# SolderingStation-v2_2026-06-25.net
KiCad netlist of a schematic drawn in Altium Designer
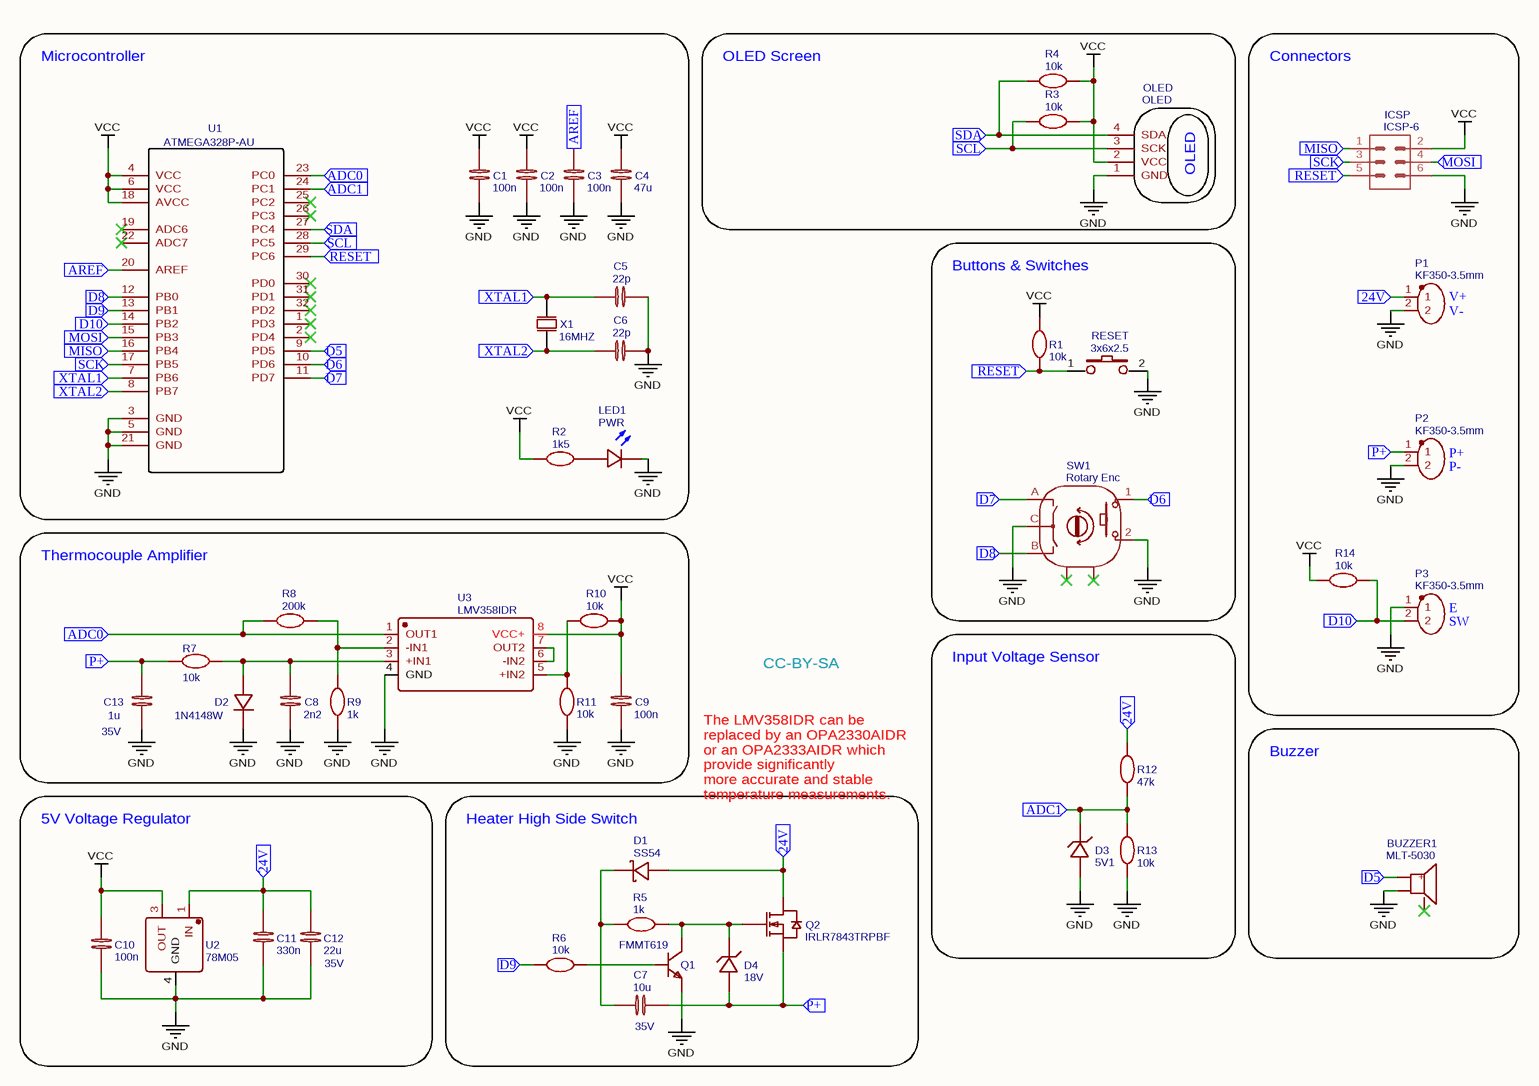
[diagram p0: SolderingStation-v2_2026-06-25.schdoc]

(export (version "E")
  (design (tool "Eeschema 10.0.6"))
  (components
    (comp (ref "BUZZER1")
      (value "MLT-5030")
      (footprint "MLT-5030")
      (fields (field (name "MANUFACTURER") "HNDZ"))
      (libsource (lib "altium-import") (part "root_0_MLT-5030_"))
    )
    (comp (ref "C1")
      (value "100n")
      (footprint "0603")
      (fields (field (name "MANUFACTURER PART") "CC0603KRX7R9BB104") (field (name "MANUFACTURER") "YAGEO"))
      (libsource (lib "altium-import") (part "root_0_100n_"))
    )
    (comp (ref "C2")
      (value "100n")
      (footprint "0603")
      (fields (field (name "MANUFACTURER PART") "CC0603KRX7R9BB104") (field (name "MANUFACTURER") "YAGEO"))
      (libsource (lib "altium-import") (part "root_0_100n_"))
    )
    (comp (ref "C3")
      (value "100n")
      (footprint "0603")
      (fields (field (name "MANUFACTURER PART") "CC0603KRX7R9BB104") (field (name "MANUFACTURER") "YAGEO"))
      (libsource (lib "altium-import") (part "root_0_100n_"))
    )
    (comp (ref "C4")
      (value "47u")
      (footprint "1206")
      (fields (field (name "MANUFACTURER PART") "1206F476M100NT") (field (name "MANUFACTURER") "FH"))
      (libsource (lib "altium-import") (part "root_0_47u_"))
    )
    (comp (ref "C5")
      (value "22p")
      (footprint "0603")
      (fields (field (name "MANUFACTURER PART") "CL10C220JB8NNNC") (field (name "MANUFACTURER") "SAMSUNG"))
      (libsource (lib "altium-import") (part "root_1_22p_"))
    )
    (comp (ref "C6")
      (value "22p")
      (footprint "0603")
      (fields (field (name "MANUFACTURER PART") "CL10C220JB8NNNC") (field (name "MANUFACTURER") "SAMSUNG"))
      (libsource (lib "altium-import") (part "root_1_22p_"))
    )
    (comp (ref "C7")
      (value "10u")
      (footprint "1206")
      (fields
        (field (name "MANUFACTURER PART") "GMK316BJ106KL-T")
        (field (name "MANUFACTURER") "Taiyo Yuden")
      )
      (libsource (lib "altium-import") (part "root_1_10u_"))
    )
    (comp (ref "C8")
      (value "2n2")
      (footprint "0603")
      (fields (field (name "MANUFACTURER PART") "0603B222K500NT") (field (name "MANUFACTURER") "FH"))
      (libsource (lib "altium-import") (part "root_0_2n2_"))
    )
    (comp (ref "C9")
      (value "100n")
      (footprint "0603")
      (fields (field (name "MANUFACTURER PART") "CC0603KRX7R9BB104") (field (name "MANUFACTURER") "YAGEO"))
      (libsource (lib "altium-import") (part "root_0_100n_"))
    )
    (comp (ref "C10")
      (value "100n")
      (footprint "0603")
      (fields (field (name "MANUFACTURER PART") "CC0603KRX7R9BB104") (field (name "MANUFACTURER") "YAGEO"))
      (libsource (lib "altium-import") (part "root_0_100n_"))
    )
    (comp (ref "C11")
      (value "330n")
      (footprint "0603")
      (fields (field (name "MANUFACTURER PART") "C1608X7R1H334KT000E") (field (name "MANUFACTURER") "TDK"))
      (libsource (lib "altium-import") (part "root_0_330n_"))
    )
    (comp (ref "C12")
      (value "22u")
      (footprint "1206")
      (fields (field (name "MANUFACTURER PART") "C3216X5R1V226MTJ00E") (field (name "MANUFACTURER") "TDK"))
      (libsource (lib "altium-import") (part "root_0_22u_"))
    )
    (comp (ref "C13")
      (value "1u")
      (footprint "0603")
      (fields (field (name "MANUFACTURER PART") "CL10A105KB8NNNC") (field (name "MANUFACTURER") "SAMSUNG"))
      (libsource (lib "altium-import") (part "root_0_1u_"))
    )
    (comp (ref "D1")
      (value "SS54")
      (footprint "DIODE-SMA(DO-214AC)")
      (fields (field (name "MANUFACTURER") "Jingdao") (field (name "CONTRIBUTOR") "LCSC"))
      (libsource (lib "altium-import") (part "root_0_SS54_"))
    )
    (comp (ref "D2")
      (value "1N4148W")
      (footprint "DIODE-SOD-123")
      (fields
        (field (name "MANUFACTURER") "Vishay Intertech")
        (field (name "MANUFACTURER PART") "1N4148W-E3-08")
        (field (name "CONTRIBUTOR") "LCSC")
      )
      (libsource (lib "altium-import") (part "root_3_1N4148W_"))
    )
    (comp (ref "D3")
      (value "5V1")
      (footprint "ZENER-SOD-123")
      (fields
        (field (name "MANUFACTURER") "SEMTECH")
        (field (name "MANUFACTURER PART") "MM1Z5V1")
        (field (name "CONTRIBUTOR") "LCSC")
      )
      (libsource (lib "altium-import") (part "root_1_5V1_"))
    )
    (comp (ref "D4")
      (value "18V")
      (footprint "ZENER-SOD-123")
      (fields
        (field (name "MANUFACTURER") "Jingdao")
        (field (name "MANUFACTURER PART") "MM1Z18")
        (field (name "CONTRIBUTOR") "LCSC")
      )
      (libsource (lib "altium-import") (part "root_1_18V_"))
    )
    (comp (ref "ICSP")
      (value "ICSP-6")
      (footprint "ICSP-6")
      (fields (field (name "MANUFACTURER PART") "?") (field (name "CONTRIBUTOR") "DowntownCB"))
      (libsource (lib "altium-import") (part "root_2_ICSP-6_"))
    )
    (comp (ref "LED1")
      (value "PWR")
      (footprint "LED0603")
      (fields
        (field (name "MANUFACTURER") "EVERLIGHT")
        (field (name "MANUFACTURER PART") "19-217/BHC-ZL1M2RY/3T")
      )
      (libsource (lib "altium-import") (part "root_0_PWR_"))
    )
    (comp (ref "OLED")
      (value "OLED")
      (footprint "I2C - OLED 0.96\" 128X64")
      (fields (field (name "MANUFACTURER PART") "SSD1306 I2C OLED") (field (name "CONTRIBUTOR") "stozk"))
      (libsource (lib "altium-import") (part "root_1_OLED_"))
    )
    (comp (ref "P1")
      (value "KF350-3.5mm")
      (footprint "KF350-2P")
      (fields (field (name "MANUFACTURER") "ReliaPro") (field (name "MANUFACTURER PART") "WJ2EDGVC-5.08-2P"))
      (libsource (lib "altium-import") (part "root_0_KF350-3.5mm_"))
    )
    (comp (ref "P2")
      (value "KF350-3.5mm")
      (footprint "KF350-2P")
      (fields (field (name "MANUFACTURER") "ReliaPro") (field (name "MANUFACTURER PART") "WJ2EDGVC-5.08-2P"))
      (libsource (lib "altium-import") (part "root_0_KF350-3.5mm_"))
    )
    (comp (ref "P3")
      (value "KF350-3.5mm")
      (footprint "KF350-2P")
      (fields (field (name "MANUFACTURER") "ReliaPro") (field (name "MANUFACTURER PART") "WJ2EDGVC-5.08-2P"))
      (libsource (lib "altium-import") (part "root_0_KF350-3.5mm_"))
    )
    (comp (ref "Q1")
      (value "FMMT619")
      (footprint "SOT-23-3_L2.9-W1.6-P1.90-LS2.8-BR")
      (fields (field (name "MANUFACTURER") "CJ"))
      (libsource (lib "altium-import") (part "root_0_FMMT619_"))
    )
    (comp (ref "Q2")
      (value "IRLR7843TRPBF")
      (footprint "TO-252-2")
      (fields (field (name "MANUFACTURER") "IR"))
      (libsource (lib "altium-import") (part "root_0_IRLR7843TRPBF_"))
    )
    (comp (ref "R1")
      (value "10k")
      (footprint "0603")
      (fields (field (name "MANUFACTURER PART") "0603WAF1002T5E") (field (name "MANUFACTURER") "UniOhm"))
      (libsource (lib "altium-import") (part "root_1_10k_"))
    )
    (comp (ref "R2")
      (value "1k5")
      (footprint "0603")
      (fields (field (name "MANUFACTURER PART") "0603WAF1501T5E") (field (name "MANUFACTURER") "UniOhm"))
      (libsource (lib "altium-import") (part "root_0_1k5_"))
    )
    (comp (ref "R3")
      (value "10k")
      (footprint "0603")
      (fields (field (name "MANUFACTURER PART") "0603WAF1002T5E") (field (name "MANUFACTURER") "UniOhm"))
      (libsource (lib "altium-import") (part "root_0_10k_"))
    )
    (comp (ref "R4")
      (value "10k")
      (footprint "0603")
      (fields (field (name "MANUFACTURER PART") "0603WAF1002T5E") (field (name "MANUFACTURER") "UniOhm"))
      (libsource (lib "altium-import") (part "root_2_10k_"))
    )
    (comp (ref "R5")
      (value "1k")
      (footprint "1206")
      (fields (field (name "MANUFACTURER PART") "1206W4F1001T5E") (field (name "MANUFACTURER") "UniOhm"))
      (libsource (lib "altium-import") (part "root_0_1k_"))
    )
    (comp (ref "R6")
      (value "10k")
      (footprint "0603")
      (fields (field (name "MANUFACTURER PART") "0603WAF1002T5E") (field (name "MANUFACTURER") "UniOhm"))
      (libsource (lib "altium-import") (part "root_0_10k_"))
    )
    (comp (ref "R7")
      (value "10k")
      (footprint "0603")
      (fields (field (name "MANUFACTURER PART") "0603WAF1002T5E") (field (name "MANUFACTURER") "UniOhm"))
      (libsource (lib "altium-import") (part "root_0_10k_"))
    )
    (comp (ref "R8")
      (value "200k")
      (footprint "0603")
      (fields (field (name "MANUFACTURER PART") "0603WAF2003T5E") (field (name "MANUFACTURER") "UniOhm"))
      (libsource (lib "altium-import") (part "root_0_200k_"))
    )
    (comp (ref "R9")
      (value "1k")
      (footprint "0603")
      (fields (field (name "MANUFACTURER PART") "0603WAF1001T5E") (field (name "MANUFACTURER") "UniOhm"))
      (libsource (lib "altium-import") (part "root_1_1k_"))
    )
    (comp (ref "R10")
      (value "10k")
      (footprint "0603")
      (fields (field (name "MANUFACTURER PART") "0603WAF1002T5E") (field (name "MANUFACTURER") "UniOhm"))
      (libsource (lib "altium-import") (part "root_0_10k_"))
    )
    (comp (ref "R11")
      (value "10k")
      (footprint "0603")
      (fields (field (name "MANUFACTURER PART") "0603WAF1002T5E") (field (name "MANUFACTURER") "UniOhm"))
      (libsource (lib "altium-import") (part "root_1_10k_"))
    )
    (comp (ref "R12")
      (value "47k")
      (footprint "0603")
      (fields (field (name "MANUFACTURER PART") "0603WAF4702T5E") (field (name "MANUFACTURER") "UniOhm"))
      (libsource (lib "altium-import") (part "root_1_47k_"))
    )
    (comp (ref "R13")
      (value "10k")
      (footprint "0603")
      (fields (field (name "MANUFACTURER PART") "0603WAF1002T5E") (field (name "MANUFACTURER") "UniOhm"))
      (libsource (lib "altium-import") (part "root_1_10k_"))
    )
    (comp (ref "R14")
      (value "10k")
      (footprint "0603")
      (fields (field (name "MANUFACTURER PART") "0603WAF1002T5E") (field (name "MANUFACTURER") "UniOhm"))
      (libsource (lib "altium-import") (part "root_0_10k_"))
    )
    (comp (ref "RESET")
      (value "3x6x2.5")
      (footprint "KEY-3.0*6.0")
      (fields
        (field (name "MANUFACTURER") "ReliaPro")
        (field (name "MANUFACTURER PART") "3x6x2.5Red head high temperature")
      )
      (libsource (lib "altium-import") (part "root_0_3x6x2.5_"))
    )
    (comp (ref "SW1")
      (value "Rotary Enc")
      (footprint "BOURNS_PEC11R-4XXXF-SXXXX")
      (fields
        (field (name "MANUFACTURER") "BOURNS")
        (field (name "MANUFACTURER PART") "PEC11R-4015F-S0024")
        (field (name "CONTRIBUTOR") "LCSC")
      )
      (libsource (lib "altium-import") (part "root_0_Rotary Enc_"))
    )
    (comp (ref "U1")
      (value "ATMEGA328P-AU")
      (footprint "TQFP-32_7X7X08P")
      (fields (field (name "MANUFACTURER") "MICROCHIP"))
      (libsource (lib "altium-import") (part "root_0_ATMEGA328P-AU_"))
    )
    (comp (ref "U2")
      (value "78M05")
      (footprint "TO-252-2")
      (fields (field (name "MANUFACTURER") "MICRONE") (field (name "MANUFACTURER PART") "ME78M05K3G"))
      (libsource (lib "altium-import") (part "root_3_78M05_"))
    )
    (comp (ref "U3")
      (value "LMV358IDR")
      (footprint "SOP-8_150MIL")
      (fields (field (name "MANUFACTURER") "TI"))
      (libsource (lib "altium-import") (part "root_0_LMV358IDR_"))
    )
    (comp (ref "X1")
      (value "16MHZ")
      (footprint "HC-49S")
      (fields
        (field (name "MANUFACTURER") "Yangxing Tech")
        (field (name "MANUFACTURER PART") "X49SD16MSD2SI")
        (field (name "CONTRIBUTOR") "LCSC")
      )
      (libsource (lib "altium-import") (part "root_3_16MHZ_"))
    )
  )
  (nets
    (net (code "1") (name "/24V") (class "Default")
      (node (ref "C11") (pin "1") (pinfunction "1_1") (pintype "passive"))
      (node (ref "C12") (pin "1") (pinfunction "1_1") (pintype "passive"))
      (node (ref "D1") (pin "1") (pinfunction "A_1") (pintype "passive"))
      (node (ref "P1") (pin "1") (pinfunction "1_1") (pintype "passive"))
      (node (ref "Q2") (pin "4") (pinfunction "D_4") (pintype "passive"))
      (node (ref "R12") (pin "2") (pinfunction "2_2") (pintype "passive"))
      (node (ref "U2") (pin "1") (pinfunction "IN_1") (pintype "passive"))
    )
    (net (code "2") (name "/ADC0") (class "Default")
      (node (ref "R8") (pin "1") (pinfunction "1_1") (pintype "passive"))
      (node (ref "U1") (pin "23") (pinfunction "PC0_23") (pintype "passive"))
      (node (ref "U3") (pin "1") (pinfunction "OUT1_1") (pintype "passive"))
    )
    (net (code "3") (name "/ADC1") (class "Default")
      (node (ref "D3") (pin "2") (pinfunction "K_2") (pintype "passive"))
      (node (ref "R12") (pin "1") (pinfunction "1_1") (pintype "passive"))
      (node (ref "R13") (pin "2") (pinfunction "2_2") (pintype "passive"))
      (node (ref "U1") (pin "24") (pinfunction "PC1_24") (pintype "passive"))
    )
    (net (code "4") (name "/AREF") (class "Default")
      (node (ref "C3") (pin "1") (pinfunction "1_1") (pintype "passive"))
      (node (ref "U1") (pin "20") (pinfunction "AREF_20") (pintype "passive"))
    )
    (net (code "5") (name "/D5") (class "Default")
      (node (ref "BUZZER1") (pin "1") (pinfunction "+_1") (pintype "passive"))
      (node (ref "U1") (pin "9") (pinfunction "PD5_9") (pintype "passive"))
    )
    (net (code "6") (name "/D6") (class "Default")
      (node (ref "SW1") (pin "1") (pinfunction "1_1") (pintype "passive"))
      (node (ref "U1") (pin "10") (pinfunction "PD6_10") (pintype "passive"))
    )
    (net (code "7") (name "/D7") (class "Default")
      (node (ref "SW1") (pin "A") (pinfunction "A_A") (pintype "passive"))
      (node (ref "U1") (pin "11") (pinfunction "PD7_11") (pintype "passive"))
    )
    (net (code "8") (name "/D8") (class "Default")
      (node (ref "SW1") (pin "B") (pinfunction "B_B") (pintype "passive"))
      (node (ref "U1") (pin "12") (pinfunction "PB0_12") (pintype "passive"))
    )
    (net (code "9") (name "/D9") (class "Default")
      (node (ref "R6") (pin "1") (pinfunction "1_1") (pintype "passive"))
      (node (ref "U1") (pin "13") (pinfunction "PB1_13") (pintype "passive"))
    )
    (net (code "10") (name "/D10") (class "Default")
      (node (ref "P3") (pin "2") (pinfunction "2_2") (pintype "passive"))
      (node (ref "R14") (pin "2") (pinfunction "2_2") (pintype "passive"))
      (node (ref "U1") (pin "14") (pinfunction "PB2_14") (pintype "passive"))
    )
    (net (code "11") (name "/MISO") (class "Default")
      (node (ref "ICSP") (pin "1") (pinfunction "1_1") (pintype "passive"))
      (node (ref "U1") (pin "16") (pinfunction "PB4_16") (pintype "passive"))
    )
    (net (code "12") (name "/MOSI") (class "Default")
      (node (ref "ICSP") (pin "4") (pinfunction "4_4") (pintype "passive"))
      (node (ref "U1") (pin "15") (pinfunction "PB3_15") (pintype "passive"))
    )
    (net (code "13") (name "/P+") (class "Default")
      (node (ref "C13") (pin "1") (pinfunction "1_1") (pintype "passive"))
      (node (ref "C7") (pin "2") (pinfunction "2_2") (pintype "passive"))
      (node (ref "D4") (pin "1") (pinfunction "A_1") (pintype "passive"))
      (node (ref "P2") (pin "1") (pinfunction "1_1") (pintype "passive"))
      (node (ref "Q2") (pin "3") (pinfunction "S_3") (pintype "passive"))
      (node (ref "R7") (pin "1") (pinfunction "1_1") (pintype "passive"))
    )
    (net (code "14") (name "/RESET") (class "Default")
      (node (ref "ICSP") (pin "5") (pinfunction "5_5") (pintype "passive"))
      (node (ref "R1") (pin "1") (pinfunction "1_1") (pintype "passive"))
      (node (ref "RESET") (pin "1") (pinfunction "1_1") (pintype "passive"))
      (node (ref "U1") (pin "29") (pinfunction "PC6_29") (pintype "passive"))
    )
    (net (code "15") (name "/SCK") (class "Default")
      (node (ref "ICSP") (pin "3") (pinfunction "3_3") (pintype "passive"))
      (node (ref "U1") (pin "17") (pinfunction "PB5_17") (pintype "passive"))
    )
    (net (code "16") (name "/SCL") (class "Default")
      (node (ref "OLED") (pin "3") (pinfunction "SCK_3") (pintype "passive"))
      (node (ref "R3") (pin "1") (pinfunction "1_1") (pintype "passive"))
      (node (ref "U1") (pin "28") (pinfunction "PC5_28") (pintype "passive"))
    )
    (net (code "17") (name "/SDA") (class "Default")
      (node (ref "OLED") (pin "4") (pinfunction "SDA_4") (pintype "passive"))
      (node (ref "R4") (pin "2") (pinfunction "2_2") (pintype "passive"))
      (node (ref "U1") (pin "27") (pinfunction "PC4_27") (pintype "passive"))
    )
    (net (code "18") (name "/XTAL1") (class "Default")
      (node (ref "C5") (pin "1") (pinfunction "1_1") (pintype "passive"))
      (node (ref "U1") (pin "7") (pinfunction "PB6_7") (pintype "passive"))
      (node (ref "X1") (pin "2") (pinfunction "OSC2_2") (pintype "passive"))
    )
    (net (code "19") (name "/XTAL2") (class "Default")
      (node (ref "C6") (pin "1") (pinfunction "1_1") (pintype "passive"))
      (node (ref "U1") (pin "8") (pinfunction "PB7_8") (pintype "passive"))
      (node (ref "X1") (pin "1") (pinfunction "OSC1_1") (pintype "passive"))
    )
    (net (code "20") (name "GND") (class "Default")
      (node (ref "BUZZER1") (pin "2") (pinfunction "2_2") (pintype "passive"))
      (node (ref "C1") (pin "2") (pinfunction "2_2") (pintype "passive"))
      (node (ref "C10") (pin "2") (pinfunction "2_2") (pintype "passive"))
      (node (ref "C11") (pin "2") (pinfunction "2_2") (pintype "passive"))
      (node (ref "C12") (pin "2") (pinfunction "2_2") (pintype "passive"))
      (node (ref "C13") (pin "2") (pinfunction "2_2") (pintype "passive"))
      (node (ref "C2") (pin "2") (pinfunction "2_2") (pintype "passive"))
      (node (ref "C3") (pin "2") (pinfunction "2_2") (pintype "passive"))
      (node (ref "C4") (pin "2") (pinfunction "2_2") (pintype "passive"))
      (node (ref "C5") (pin "2") (pinfunction "2_2") (pintype "passive"))
      (node (ref "C6") (pin "2") (pinfunction "2_2") (pintype "passive"))
      (node (ref "C8") (pin "2") (pinfunction "2_2") (pintype "passive"))
      (node (ref "C9") (pin "2") (pinfunction "2_2") (pintype "passive"))
      (node (ref "D2") (pin "2") (pinfunction "K_2") (pintype "passive"))
      (node (ref "D3") (pin "1") (pinfunction "A_1") (pintype "passive"))
      (node (ref "ICSP") (pin "6") (pinfunction "6_6") (pintype "passive"))
      (node (ref "LED1") (pin "2") (pinfunction "-_2") (pintype "passive"))
      (node (ref "OLED") (pin "1") (pinfunction "GND_1") (pintype "passive"))
      (node (ref "P1") (pin "2") (pinfunction "2_2") (pintype "passive"))
      (node (ref "P2") (pin "2") (pinfunction "2_2") (pintype "passive"))
      (node (ref "P3") (pin "1") (pinfunction "1_1") (pintype "passive"))
      (node (ref "Q1") (pin "2") (pinfunction "E_2") (pintype "passive"))
      (node (ref "R11") (pin "1") (pinfunction "1_1") (pintype "passive"))
      (node (ref "R13") (pin "1") (pinfunction "1_1") (pintype "passive"))
      (node (ref "R9") (pin "1") (pinfunction "1_1") (pintype "passive"))
      (node (ref "RESET") (pin "2") (pinfunction "2_2") (pintype "passive"))
      (node (ref "SW1") (pin "2") (pinfunction "2_2") (pintype "passive"))
      (node (ref "SW1") (pin "C") (pinfunction "C_C") (pintype "passive"))
      (node (ref "U1") (pin "21") (pinfunction "GND_21") (pintype "passive"))
      (node (ref "U1") (pin "3") (pinfunction "GND_3") (pintype "passive"))
      (node (ref "U1") (pin "5") (pinfunction "GND_5") (pintype "passive"))
      (node (ref "U2") (pin "4") (pinfunction "GND_4") (pintype "passive"))
      (node (ref "U3") (pin "4") (pinfunction "GND_4") (pintype "passive"))
    )
    (net (code "21") (name "Net-(D1-K)") (class "Default")
      (node (ref "C7") (pin "1") (pinfunction "1_1") (pintype "passive"))
      (node (ref "D1") (pin "2") (pinfunction "K_2") (pintype "passive"))
      (node (ref "R5") (pin "1") (pinfunction "1_1") (pintype "passive"))
    )
    (net (code "22") (name "Net-(D2-A)") (class "Default")
      (node (ref "C8") (pin "1") (pinfunction "1_1") (pintype "passive"))
      (node (ref "D2") (pin "1") (pinfunction "A_1") (pintype "passive"))
      (node (ref "R7") (pin "2") (pinfunction "2_2") (pintype "passive"))
      (node (ref "U3") (pin "3") (pinfunction "+IN1_3") (pintype "passive"))
    )
    (net (code "23") (name "Net-(D4-K)") (class "Default")
      (node (ref "D4") (pin "2") (pinfunction "K_2") (pintype "passive"))
      (node (ref "Q1") (pin "3") (pinfunction "C_3") (pintype "passive"))
      (node (ref "Q2") (pin "1") (pinfunction "G_1") (pintype "passive"))
      (node (ref "R5") (pin "2") (pinfunction "2_2") (pintype "passive"))
    )
    (net (code "24") (name "Net-(LED1-+)") (class "Default")
      (node (ref "LED1") (pin "1") (pinfunction "+_1") (pintype "passive"))
      (node (ref "R2") (pin "2") (pinfunction "2_2") (pintype "passive"))
    )
    (net (code "25") (name "Net-(Q1-B)") (class "Default")
      (node (ref "Q1") (pin "1") (pinfunction "B_1") (pintype "passive"))
      (node (ref "R6") (pin "2") (pinfunction "2_2") (pintype "passive"))
    )
    (net (code "26") (name "Net-(U3-+IN2)") (class "Default")
      (node (ref "R10") (pin "1") (pinfunction "1_1") (pintype "passive"))
      (node (ref "R11") (pin "2") (pinfunction "2_2") (pintype "passive"))
      (node (ref "U3") (pin "5") (pinfunction "+IN2_5") (pintype "passive"))
    )
    (net (code "27") (name "Net-(U3--IN1)") (class "Default")
      (node (ref "R8") (pin "2") (pinfunction "2_2") (pintype "passive"))
      (node (ref "R9") (pin "2") (pinfunction "2_2") (pintype "passive"))
      (node (ref "U3") (pin "2") (pinfunction "-IN1_2") (pintype "passive"))
    )
    (net (code "28") (name "Net-(U3--IN2)") (class "Default")
      (node (ref "U3") (pin "6") (pinfunction "-IN2_6") (pintype "passive"))
      (node (ref "U3") (pin "7") (pinfunction "OUT2_7") (pintype "passive"))
    )
    (net (code "29") (name "VCC") (class "Default")
      (node (ref "C1") (pin "1") (pinfunction "1_1") (pintype "passive"))
      (node (ref "C10") (pin "1") (pinfunction "1_1") (pintype "passive"))
      (node (ref "C2") (pin "1") (pinfunction "1_1") (pintype "passive"))
      (node (ref "C4") (pin "1") (pinfunction "1_1") (pintype "passive"))
      (node (ref "C9") (pin "1") (pinfunction "1_1") (pintype "passive"))
      (node (ref "ICSP") (pin "2") (pinfunction "2_2") (pintype "passive"))
      (node (ref "OLED") (pin "2") (pinfunction "VCC_2") (pintype "passive"))
      (node (ref "R1") (pin "2") (pinfunction "2_2") (pintype "passive"))
      (node (ref "R10") (pin "2") (pinfunction "2_2") (pintype "passive"))
      (node (ref "R14") (pin "1") (pinfunction "1_1") (pintype "passive"))
      (node (ref "R2") (pin "1") (pinfunction "1_1") (pintype "passive"))
      (node (ref "R3") (pin "2") (pinfunction "2_2") (pintype "passive"))
      (node (ref "R4") (pin "1") (pinfunction "1_1") (pintype "passive"))
      (node (ref "U1") (pin "18") (pinfunction "AVCC_18") (pintype "passive"))
      (node (ref "U1") (pin "4") (pinfunction "VCC_4") (pintype "passive"))
      (node (ref "U1") (pin "6") (pinfunction "VCC_6") (pintype "passive"))
      (node (ref "U2") (pin "3") (pinfunction "OUT_3") (pintype "passive"))
      (node (ref "U3") (pin "8") (pinfunction "VCC+_8") (pintype "passive"))
    )
    (net (code "30") (name "unconnected-(BUZZER1-NC-Pad3)") (class "Default")
      (node (ref "BUZZER1") (pin "3") (pinfunction "NC_3") (pintype "passive+no_connect"))
    )
    (net (code "31") (name "unconnected-(SW1-PadMT1)") (class "Default")
      (node (ref "SW1") (pin "MT1") (pinfunction "MT1_MT1") (pintype "passive+no_connect"))
    )
    (net (code "32") (name "unconnected-(SW1-PadMT2)") (class "Default")
      (node (ref "SW1") (pin "MT2") (pinfunction "MT2_MT2") (pintype "passive+no_connect"))
    )
    (net (code "33") (name "unconnected-(U1-ADC6-Pad19)") (class "Default")
      (node (ref "U1") (pin "19") (pinfunction "ADC6_19") (pintype "passive+no_connect"))
    )
    (net (code "34") (name "unconnected-(U1-ADC7-Pad22)") (class "Default")
      (node (ref "U1") (pin "22") (pinfunction "ADC7_22") (pintype "passive+no_connect"))
    )
    (net (code "35") (name "unconnected-(U1-PC2-Pad25)") (class "Default")
      (node (ref "U1") (pin "25") (pinfunction "PC2_25") (pintype "passive+no_connect"))
    )
    (net (code "36") (name "unconnected-(U1-PC3-Pad26)") (class "Default")
      (node (ref "U1") (pin "26") (pinfunction "PC3_26") (pintype "passive+no_connect"))
    )
    (net (code "37") (name "unconnected-(U1-PD0-Pad30)") (class "Default")
      (node (ref "U1") (pin "30") (pinfunction "PD0_30") (pintype "passive+no_connect"))
    )
    (net (code "38") (name "unconnected-(U1-PD1-Pad31)") (class "Default")
      (node (ref "U1") (pin "31") (pinfunction "PD1_31") (pintype "passive+no_connect"))
    )
    (net (code "39") (name "unconnected-(U1-PD2-Pad32)") (class "Default")
      (node (ref "U1") (pin "32") (pinfunction "PD2_32") (pintype "passive+no_connect"))
    )
    (net (code "40") (name "unconnected-(U1-PD3-Pad1)") (class "Default")
      (node (ref "U1") (pin "1") (pinfunction "PD3_1") (pintype "passive+no_connect"))
    )
    (net (code "41") (name "unconnected-(U1-PD4-Pad2)") (class "Default")
      (node (ref "U1") (pin "2") (pinfunction "PD4_2") (pintype "passive+no_connect"))
    )
  )
)
